# DC_Power_Regulation.net
KiCad netlist of a schematic drawn in Altium Designer
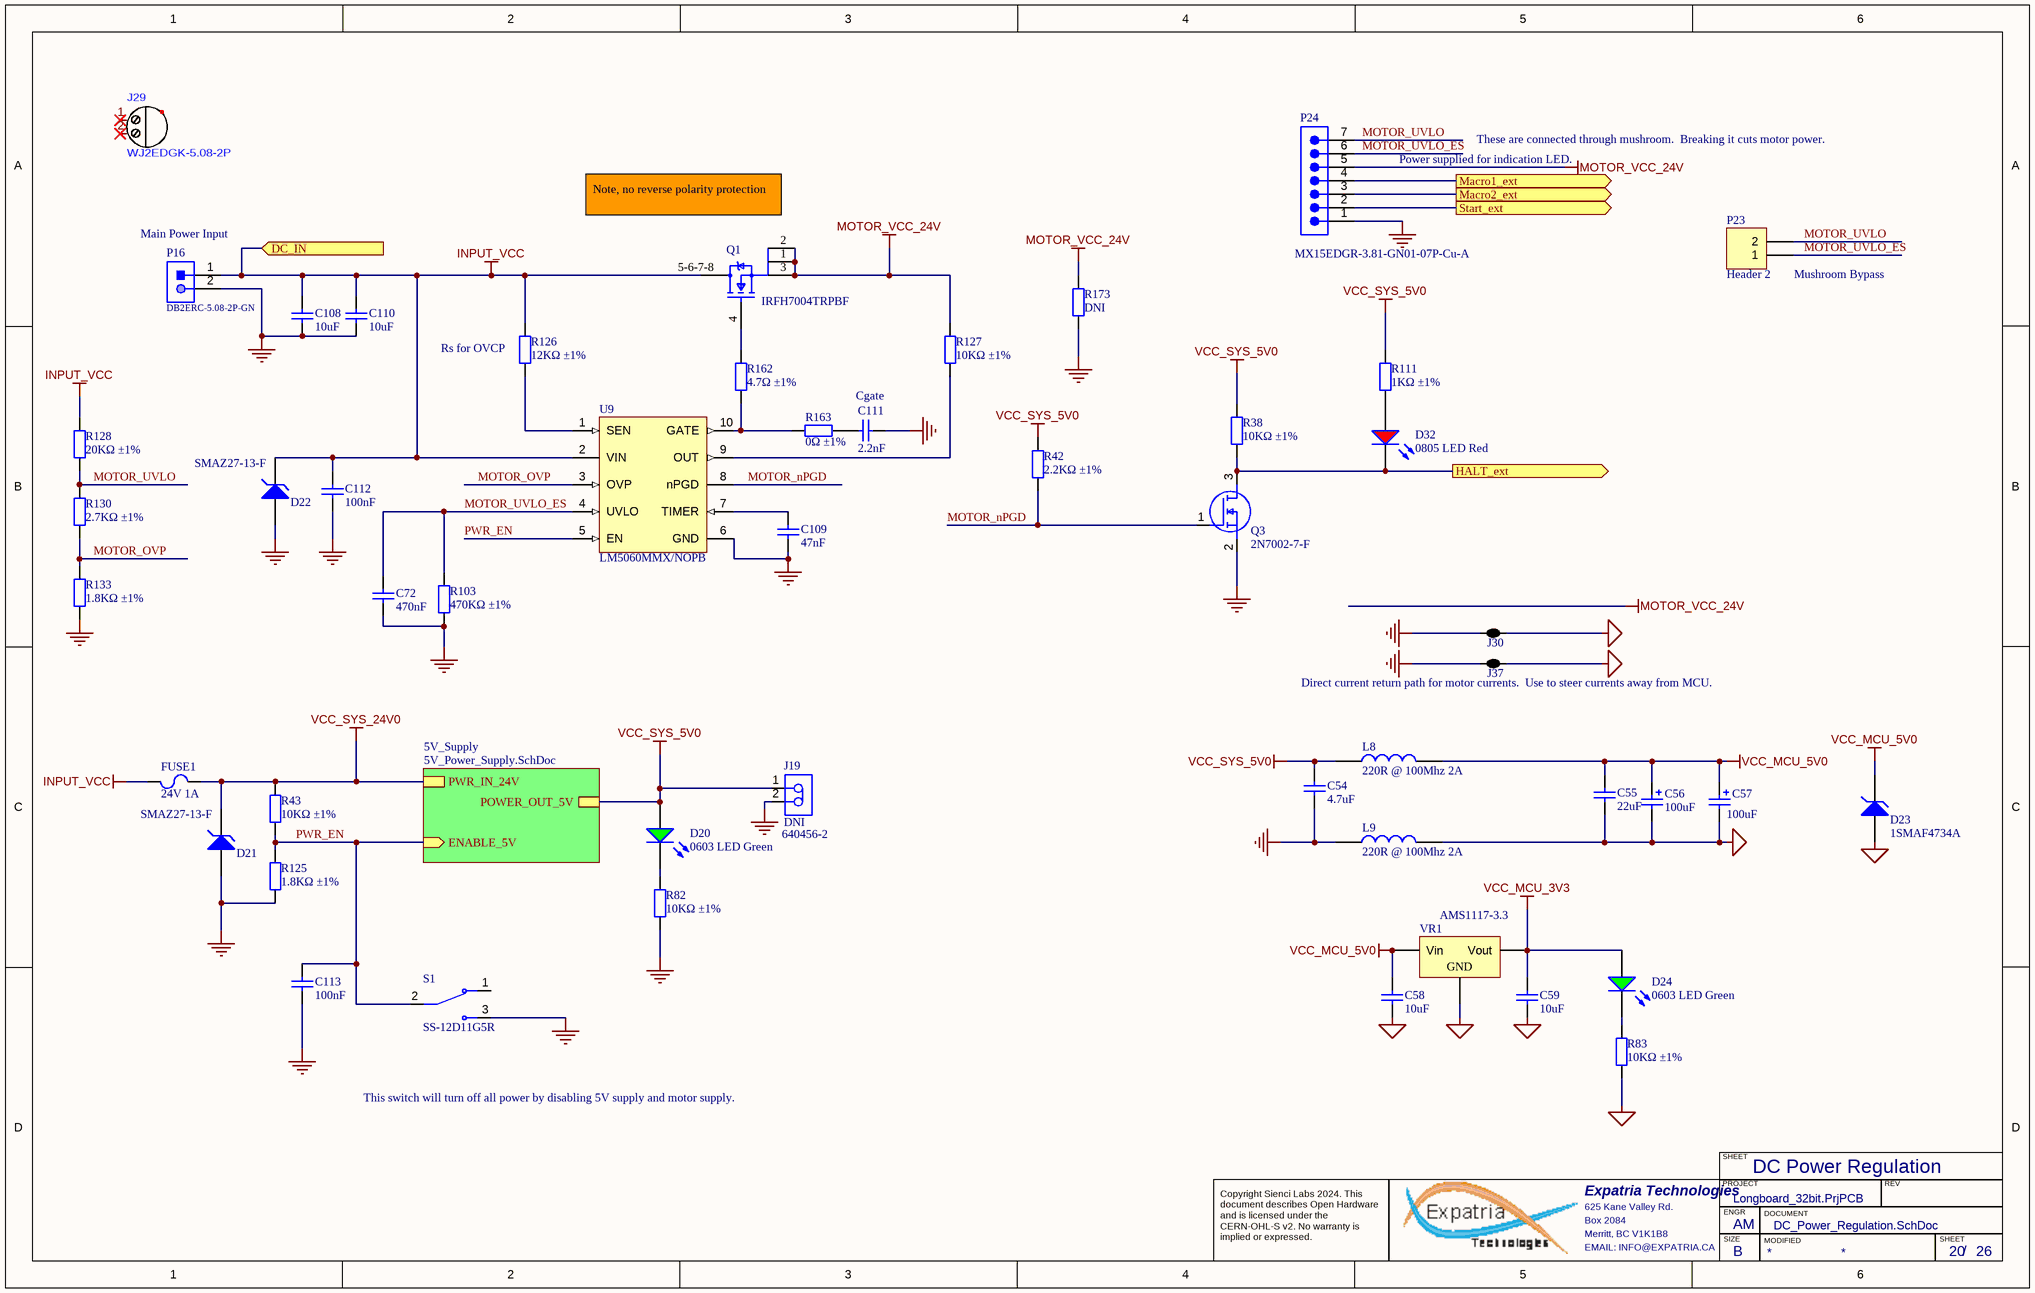
[diagram p0: DC_Power_Regulation.SchDoc]

(export (version "E")
  (design (tool "Eeschema 10.0.6"))
  (components
    (comp (ref "C54")
      (value "4.7uF")
      (footprint "0603_C")
      (description "16V 4.7uF X5R ±10% 0603 Multilayer Ceramic Capacitors MLCC - SMD/SMT ROHS")
      (fields (field (name "MANUFACTURER") "Samsung Electro-Mechanics") (field (name "TOLERANCE") "10%"))
      (libsource (lib "Sienci_Labs") (part "0603 4.7uF (475) 10% 16V"))
    )
    (comp (ref "C55")
      (value "22uF")
      (footprint "0805_C")
      (description "25V 22uF X5R ±20% 0805 Multilayer Ceramic Capacitors MLCC - SMD/SMT ROHS")
      (fields (field (name "MANUFACTURER") "Samsung Electro-Mechanics") (field (name "TOLERANCE") "20%"))
      (libsource (lib "Sienci_Labs") (part "0805 22uF (226) 20% 25V"))
    )
    (comp (ref "C56")
      (value "100uF")
      (footprint "CASE-B_3528")
      (description "Tantalum capacitor")
      (fields (field (name "MANUFACTURER") "AVX") (field (name "PARTNUMBER") "TAJB107K006RNJ"))
      (libsource (lib "Cap") (part "3528 100uF (107) 10% 6.3V"))
    )
    (comp (ref "C57")
      (value "100uF")
      (footprint "WCAP-ASLI_D6.3H7.7")
      (fields
        (field (name "MANUFACTURER") "Capxon International Elec")
        (field (name "MANUFACTURER PART NUMBER") "HV101M035E077ETR")
      )
      (libsource (lib "IQAnalog") (part "865080445010"))
    )
    (comp (ref "C58")
      (value "10uF")
      (footprint "1206_C")
      (description "50V 10uF X5R ±10% 1206 Multilayer Ceramic Capacitors MLCC - SMD/SMT ROHS")
      (fields
        (field (name "MANUFACTURER") "Samsung Electro-Mechanics")
        (field (name "MANUFACTURER PART NUMBER") "CL31A106KBHNNNE")
      )
      (libsource (lib "Sienci_Labs") (part "1206 10uF (106) 10% 50V"))
    )
    (comp (ref "C59")
      (value "10uF")
      (footprint "1206_C")
      (description "50V 10uF X5R ±10% 1206 Multilayer Ceramic Capacitors MLCC - SMD/SMT ROHS")
      (fields
        (field (name "MANUFACTURER") "Samsung Electro-Mechanics")
        (field (name "MANUFACTURER PART NUMBER") "CL31A106KBHNNNE")
      )
      (libsource (lib "Sienci_Labs") (part "1206 10uF (106) 10% 50V"))
    )
    (comp (ref "C72")
      (value "470nF")
      (footprint "0603_C")
      (description "Chip capacitors")
      (fields (field (name "MANUFACTURER") "Samsung Electro-Mechanics") (field (name "TOLERANCE") "10%"))
      (libsource (lib "Sienci_Labs") (part "0603 470nF (474) 10% 25V"))
    )
    (comp (ref "C108")
      (value "10uF")
      (footprint "1206_C")
      (description "50V 10uF X5R ±10% 1206 Multilayer Ceramic Capacitors MLCC - SMD/SMT ROHS")
      (fields (field (name "MANUFACTURER") "Samsung Electro-Mechanics") (field (name "TOLERANCE") "10%"))
      (libsource (lib "Sienci_Labs") (part "1206 10uF (106) 10% 50V"))
    )
    (comp (ref "C109")
      (value "47nF")
      (footprint "0603_C")
      (description "Chip capacitors")
      (fields
        (field (name "MANUFACTURER") "Samsung Electro-Mechanics")
        (field (name "PARTNUMBER") "CL10B473KB8NNNC")
      )
      (libsource (lib "Cap") (part "0603 47nF (473) 10% 50V"))
    )
    (comp (ref "C110")
      (value "10uF")
      (footprint "1206_C")
      (description "50V 10uF X5R ±10% 1206 Multilayer Ceramic Capacitors MLCC - SMD/SMT ROHS")
      (fields (field (name "MANUFACTURER") "Samsung Electro-Mechanics") (field (name "TOLERANCE") "10%"))
      (libsource (lib "Sienci_Labs") (part "1206 10uF (106) 10% 50V"))
    )
    (comp (ref "C111")
      (value "2.2nF")
      (footprint "0402_C")
      (description "Chip capacitor")
      (fields
        (field (name "MANUFACTURER") "Guangdong Fenghua Advanced Tech")
        (field (name "TOLERANCE") "10%")
      )
      (libsource (lib "Cap") (part "0402 2.2nF (222) 10% 50V"))
    )
    (comp (ref "C112")
      (value "100nF")
      (footprint "0603_C")
      (description "50V 100nF X7R ±10% 0603 Multilayer Ceramic Capacitors MLCC - SMD/SMT ROHS")
      (fields (field (name "MANUFACTURER") "YAGEO") (field (name "TOLERANCE") "10%"))
      (libsource (lib "Sienci_Labs") (part "0603 100nF (104) 10% 50V"))
    )
    (comp (ref "C113")
      (value "100nF")
      (footprint "0603_C")
      (description "50V 100nF X7R ±10% 0603 Multilayer Ceramic Capacitors MLCC - SMD/SMT ROHS")
      (fields (field (name "MANUFACTURER") "YAGEO") (field (name "TOLERANCE") "10%"))
      (libsource (lib "Sienci_Labs") (part "0603 100nF (104) 10% 50V"))
    )
    (comp (ref "D20")
      (value "0603 LED Green")
      (footprint "0603_LED_S1 - GREEN")
      (fields
        (field (name "MANUFACTURER PART NUMBER") "19-217/GHC-YR1S2/3T")
        (field (name "MANUFACTURER") "Everlight Elec")
      )
      (libsource (lib "Sienci_Labs") (part "19-217/GHC-YR1S2/3T"))
    )
    (comp (ref "D21")
      (value "SMAZ27-13-F")
      (footprint "DIOM5226X240N")
      (description "27V ±5% 1W 500nA @ 20.5V SMA(DO-214AC) Zener Diodes RoHS")
      (fields (field (name "MANUFACTURER") "Diodes Incorporated"))
      (libsource (lib "PrintNC_GRBLHAL_Breakout") (part "BZT52C27"))
    )
    (comp (ref "D22")
      (value "SMAZ27-13-F")
      (footprint "DIOM5226X240N")
      (description "27V ±5% 1W 500nA @ 20.5V SMA(DO-214AC) Zener Diodes RoHS")
      (fields (field (name "MANUFACTURER") "Diodes Incorporated"))
      (libsource (lib "PrintNC_GRBLHAL_Breakout") (part "BZT52C27"))
    )
    (comp (ref "D23")
      (value "1SMAF4734A")
      (footprint "DIOM5226X240N")
      (description "27V ±5% 1W 500nA @ 20.5V SMA(DO-214AC) Zener Diodes RoHS")
      (fields (field (name "MANUFACTURER") "Shandong Jingdao Microelectronics"))
      (libsource (lib "PrintNC_GRBLHAL_Breakout") (part "BZT52C27"))
    )
    (comp (ref "D24")
      (value "0603 LED Green")
      (footprint "0603_LED_S1 - GREEN")
      (fields
        (field (name "MANUFACTURER PART NUMBER") "19-217/GHC-YR1S2/3T")
        (field (name "MANUFACTURER") "Everlight Elec")
      )
      (libsource (lib "Sienci_Labs") (part "19-217/GHC-YR1S2/3T"))
    )
    (comp (ref "D32")
      (value "0805 LED Red")
      (footprint "0805_LED_S1 - RED")
      (description "Red 0805 Light Emitting Diodes (LED) ROHS")
      (fields
        (field (name "MANUFACTURER") "Foshan NationStar Optoelectronics")
        (field (name "MANUFACTURER PART NUMBER") "NCD0805R1")
      )
      (libsource (lib "Sienci_Labs") (part "0805 LED Red"))
    )
    (comp (ref "FUSE1")
      (value "24V 1A")
      (footprint "1206_C")
      (description "24V 1A 0.1s 1206 PTC Resettable Fuses RoHS")
      (fields
        (field (name "MANUFACTURER") "Jinrui Electronic Materials Co.")
        (field (name "PARTNUMBER") "JK-nSMD050-24")
      )
      (libsource (lib "PrintNC_GRBLHAL_Breakout") (part "JK-nSMD050-24"))
    )
    (comp (ref "J19")
      (value "DNI")
      (footprint "TECO-640456-2_V")
      (fields (field (name "MANUFACTURER") "TE Connectivity") (field (name "ALTIUM_VALUE") "640456-2"))
      (libsource (lib "Altium Content Vault") (part "CN-2P-F-QF2"))
    )
    (comp (ref "J29")
      (value "WJ2EDGK-5.08-2P")
      (description "5.08mm Green Plug P=5.08mm Pluggable System Terminal Block ROHS")
      (fields (field (name "MANUFACTURER") "Kangnex"))
      (libsource (lib "Sienci_Labs") (part "WJ2EDGK-5.08-2P"))
    )
    (comp (ref "J30")
      (value "2 way net tie junction")
      (footprint "2way_HP")
      (libsource (lib "NetTie") (part "2way"))
    )
    (comp (ref "J37")
      (value "2 way net tie junction")
      (footprint "2way_HP")
      (libsource (lib "NetTie") (part "2way"))
    )
    (comp (ref "L8")
      (value "220R @ 100Mhz 2A")
      (footprint "0805_R")
      (description "150mΩ ±25% 220Ω@100MHz 0805 Ferrite Beads ROHS")
      (fields
        (field (name "MANUFACTURER PART NUMBER") "CBW201209U221T")
        (field (name "MANUFACTURER") "FH (Guangdong Fenghua Advanced Tech)")
      )
      (libsource (lib "Sienci_Labs") (part "CBW201209U221T"))
    )
    (comp (ref "L9")
      (value "220R @ 100Mhz 2A")
      (footprint "0805_R")
      (description "150mΩ ±25% 220Ω@100MHz 0805 Ferrite Beads ROHS")
      (fields
        (field (name "MANUFACTURER PART NUMBER") "CBW201209U221T")
        (field (name "MANUFACTURER") "FH (Guangdong Fenghua Advanced Tech)")
      )
      (libsource (lib "Sienci_Labs") (part "CBW201209U221T"))
    )
    (comp (ref "P16")
      (value "DB2ERC-5.08-2P-GN")
      (footprint "CONN-TH_2P-P5.08_DB2ERC-5.08-2P")
      (fields (field (name "MANUFACTURER") "Dibo"))
      (libsource (lib "Sienci_Labs") (part "DB2ERC-5.08-2P-GN"))
    )
    (comp (ref "P23")
      (value "Header 2")
      (footprint "HDR1X2")
      (description "Straight Square Pins 2 2.54mm Black Brass 1x2P Plugin,P=2.54mm Pin Headers ROHS")
      (fields
        (field (name "MANUFACTURER") "MOLEX")
        (field (name "MANUFACTURER PART NUMBER") "22284020")
        (field (name "PUBLISHER") "Altium Limited")
      )
      (libsource (lib "Sienci_Labs") (part "Header 2"))
    )
    (comp (ref "P24")
      (value "MX15EDGR-3.81-GN01-07P-Cu-A")
      (footprint "691322310007")
      (fields (field (name "MANUFACTURER") "MAX"))
      (libsource (lib "Sienci_Labs") (part "MX15EDGR-3.81-GN01-07P-Cu-A"))
    )
    (comp (ref "Q1")
      (value "IRFH7004TRPBF")
      (footprint "FP-PG-TDSON-8-MFG")
      (description "MOSFET N-CH 40V 100A 8PQFN")
      (libsource (lib "MOS") (part "IRFH7004TRPBF"))
    )
    (comp (ref "Q3")
      (value "2N7002-7-F")
      (footprint "SOT-23(SOT-23-3)")
      (description "60V 115mA 7.5Ω@5V,50mA 370mW N Channel SOT-23 MOSFETs ROHS")
      (fields (field (name "MANUFACTURER") "Diodes Inc.") (field (name "MOUSER PART NUMBER") "621-2N7002-F"))
      (libsource (lib "Sienci_Labs") (part "2N7002-7-F"))
    )
    (comp (ref "R38")
      (value "10KΩ ±1%")
      (footprint "0603_R")
      (description "Chip resistor")
      (fields (field (name "MANUFACTURER") "Uniroyal Elec") (field (name "PARTNUMBER") "0603WAF1002T5E"))
      (libsource (lib "RES") (part "0603 10K (1002) 1%"))
    )
    (comp (ref "R42")
      (value "2.2KΩ ±1%")
      (footprint "0603_R")
      (description "Chip resistor")
      (fields (field (name "MANUFACTURER") "Uniroyal Elec") (field (name "PARTNUMBER") "0603WAF2201T5E"))
      (libsource (lib "RES") (part "0603 2.2K (2201) 1%"))
    )
    (comp (ref "R43")
      (value "10KΩ ±1%")
      (footprint "0603_R")
      (description "Chip resistor")
      (fields (field (name "MANUFACTURER") "Uniroyal Elec") (field (name "PARTNUMBER") "0603WAF1002T5E"))
      (libsource (lib "RES") (part "0603 10K (1002) 1%"))
    )
    (comp (ref "R82")
      (value "10KΩ ±1%")
      (footprint "0603_R")
      (description "Chip resistor")
      (fields (field (name "MANUFACTURER") "Uniroyal Elec") (field (name "PARTNUMBER") "0603WAF1002T5E"))
      (libsource (lib "RES") (part "0603 10K (1002) 1%"))
    )
    (comp (ref "R83")
      (value "10KΩ ±1%")
      (footprint "0603_R")
      (description "Chip resistor")
      (fields (field (name "MANUFACTURER") "Uniroyal Elec") (field (name "PARTNUMBER") "0603WAF1002T5E"))
      (libsource (lib "RES") (part "0603 10K (1002) 1%"))
    )
    (comp (ref "R103")
      (value "470KΩ ±1%")
      (footprint "0603_R")
      (description "Chip resistor")
      (fields (field (name "MANUFACTURER") "Uniroyal Elec") (field (name "PARTNUMBER") "0603WAF4703T5E"))
      (libsource (lib "RES") (part "0603 470K (4703) 1%"))
    )
    (comp (ref "R111")
      (value "1KΩ ±1%")
      (footprint "0603_R")
      (description "Chip resistor")
      (fields (field (name "MANUFACTURER") "Uniroyal Elec") (field (name "PARTNUMBER") "0603WAF1001T5E"))
      (libsource (lib "RES") (part "0603 1K (1001) 1%"))
    )
    (comp (ref "R125")
      (value "1.8KΩ ±1%")
      (footprint "0603_R")
      (description "Chip resistor")
      (fields (field (name "MANUFACTURER") "Uniroyal Elec") (field (name "PARTNUMBER") "0603WAF1801T5E"))
      (libsource (lib "RES") (part "0603 1.8K (1801) 1%"))
    )
    (comp (ref "R126")
      (value "12KΩ ±1%")
      (footprint "0603_R")
      (description "Chip resistor")
      (fields (field (name "MANUFACTURER") "Uniroyal Elec") (field (name "PARTNUMBER") "0603WAF1202T5E"))
      (libsource (lib "RES") (part "0603 12K (1202) 1%"))
    )
    (comp (ref "R127")
      (value "10KΩ ±1%")
      (footprint "0603_R")
      (description "Chip resistor")
      (fields (field (name "MANUFACTURER") "Uniroyal Elec") (field (name "PARTNUMBER") "0603WAF1002T5E"))
      (libsource (lib "RES") (part "0603 10K (1002) 1%"))
    )
    (comp (ref "R128")
      (value "20KΩ ±1%")
      (footprint "0603_R")
      (description "Chip resistor")
      (fields (field (name "MANUFACTURER") "Uniroyal Elec") (field (name "PARTNUMBER") "0603WAF2002T5E"))
      (libsource (lib "RES") (part "0603 20K (2002) 1%"))
    )
    (comp (ref "R130")
      (value "2.7KΩ ±1%")
      (footprint "0603_R")
      (description "Chip resistor")
      (fields (field (name "MANUFACTURER") "Uniroyal Elec") (field (name "PARTNUMBER") "0603WAF2701T5E"))
      (libsource (lib "RES") (part "0603 2.7K (2701) 1%"))
    )
    (comp (ref "R133")
      (value "1.8KΩ ±1%")
      (footprint "0603_R")
      (description "Chip resistor")
      (fields (field (name "MANUFACTURER") "Uniroyal Elec") (field (name "PARTNUMBER") "0603WAF1801T5E"))
      (libsource (lib "RES") (part "0603 1.8K (1801) 1%"))
    )
    (comp (ref "R162")
      (value "4.7Ω ±1%")
      (footprint "0603_R")
      (description "Chip resistor")
      (fields (field (name "MANUFACTURER") "Uniroyal Elec") (field (name "PARTNUMBER") "0603WAF470KT5E"))
      (libsource (lib "RES") (part "0603 4.7R (4R70) 1%"))
    )
    (comp (ref "R163")
      (value "0Ω ±1%")
      (footprint "0603_R")
      (description "Chip resistor")
      (fields (field (name "MANUFACTURER") "Uniroyal Elec") (field (name "PARTNUMBER") "0603WAF0000T5E"))
      (libsource (lib "RES") (part "0603 0R (0R0) 1%"))
    )
    (comp (ref "R173")
      (value "DNI")
      (footprint "0603_R")
      (description "Chip resistor")
      (fields (field (name "MANUFACTURER") "Uniroyal Elec") (field (name "PARTNUMBER") "0603WAF1002T5E"))
      (libsource (lib "RES") (part "0603 10K (1002) 1%"))
    )
    (comp (ref "S1")
      (value "SS-12D11G5R")
      (footprint "SW_500SSP1S1M6QEA")
      (description "Shrouded 5A SPDT 125V 125V 5A 10000次 Black Plugin Slide Switches ROHS")
      (fields (field (name "MANUFACTURER") "XKB Connectivity"))
      (libsource (lib "Sienci_Labs") (part "SS-12D11G5R"))
    )
    (comp (ref "U9")
      (value "LM5060MMX/NOPB")
      (footprint "DGS0010A_N")
      (fields (field (name "MANUFACTURER") "TI National Semiconductor"))
      (libsource (lib "Sienci_Labs") (part "LM5060MMX/NOPB"))
    )
    (comp (ref "VR1")
      (value "AMS1117-3.3")
      (footprint "SOT-223")
      (description "Vout=3.3V 1A 72dB@(120Hz) (LDO)")
      (fields (field (name "MANUFACTURER") "AMS"))
      (libsource (lib "LDO") (part "SOT-223 AMS1117-3.3"))
    )
  )
  (nets
    (net (code "1") (name "/HALT_ext") (class "Default")
      (node (ref "D32") (pin "K") (pinfunction "K_K") (pintype "passive"))
      (node (ref "Q3") (pin "3") (pinfunction "D_3") (pintype "passive"))
      (node (ref "R38") (pin "1") (pinfunction "1_1") (pintype "passive"))
    )
    (net (code "2") (name "/MOTOR_OVP") (class "Default")
      (node (ref "R130") (pin "1") (pinfunction "1_1") (pintype "passive"))
      (node (ref "R133") (pin "2") (pinfunction "2_2") (pintype "passive"))
      (node (ref "U9") (pin "3") (pinfunction "OVP_3") (pintype "input"))
    )
    (net (code "3") (name "/MOTOR_UVLO") (class "Default")
      (node (ref "P23") (pin "2") (pinfunction "2_2") (pintype "passive"))
      (node (ref "P24") (pin "7") (pinfunction "7_7") (pintype "passive"))
      (node (ref "R128") (pin "1") (pinfunction "1_1") (pintype "passive"))
      (node (ref "R130") (pin "2") (pinfunction "2_2") (pintype "passive"))
    )
    (net (code "4") (name "/MOTOR_UVLO_ES") (class "Default")
      (node (ref "C72") (pin "2") (pinfunction "2_2") (pintype "passive"))
      (node (ref "P23") (pin "1") (pinfunction "1_1") (pintype "passive"))
      (node (ref "P24") (pin "6") (pinfunction "6_6") (pintype "passive"))
      (node (ref "R103") (pin "2") (pinfunction "2_2") (pintype "passive"))
      (node (ref "U9") (pin "4") (pinfunction "UVLO_4") (pintype "input"))
    )
    (net (code "5") (name "/MOTOR_nPGD") (class "Default")
      (node (ref "Q3") (pin "1") (pinfunction "G_1") (pintype "passive"))
      (node (ref "R42") (pin "1") (pinfunction "1_1") (pintype "passive"))
      (node (ref "U9") (pin "8") (pinfunction "nPGD_8") (pintype "open_collector"))
    )
    (net (code "6") (name "/Macro1_ext") (class "Default")
      (node (ref "P24") (pin "4") (pinfunction "4_4") (pintype "passive"))
    )
    (net (code "7") (name "/Macro2_ext") (class "Default")
      (node (ref "P24") (pin "3") (pinfunction "3_3") (pintype "passive"))
    )
    (net (code "8") (name "/PWR_EN") (class "Default")
      (node (ref "C113") (pin "2") (pinfunction "2_2") (pintype "passive"))
      (node (ref "R125") (pin "2") (pinfunction "2_2") (pintype "passive"))
      (node (ref "R43") (pin "1") (pinfunction "1_1") (pintype "passive"))
      (node (ref "S1") (pin "2") (pinfunction "COM_2") (pintype "passive"))
      (node (ref "U9") (pin "5") (pinfunction "EN_5") (pintype "input"))
    )
    (net (code "9") (name "/Start_ext") (class "Default")
      (node (ref "P24") (pin "2") (pinfunction "2_2") (pintype "passive"))
    )
    (net (code "10") (name "GND") (class "Default")
      (node (ref "C108") (pin "1") (pinfunction "1_1") (pintype "passive"))
      (node (ref "C109") (pin "1") (pinfunction "1_1") (pintype "passive"))
      (node (ref "C110") (pin "1") (pinfunction "1_1") (pintype "passive"))
      (node (ref "C111") (pin "1") (pinfunction "1_1") (pintype "passive"))
      (node (ref "C112") (pin "1") (pinfunction "1_1") (pintype "passive"))
      (node (ref "C113") (pin "1") (pinfunction "1_1") (pintype "passive"))
      (node (ref "C54") (pin "1") (pinfunction "1_1") (pintype "passive"))
      (node (ref "C72") (pin "1") (pinfunction "1_1") (pintype "passive"))
      (node (ref "D21") (pin "1") (pinfunction "A_1") (pintype "passive"))
      (node (ref "D22") (pin "1") (pinfunction "A_1") (pintype "passive"))
      (node (ref "J19") (pin "2") (pinfunction "2_2") (pintype "passive"))
      (node (ref "J30") (pin "1") (pinfunction "1_1") (pintype "passive"))
      (node (ref "J37") (pin "1") (pinfunction "1_1") (pintype "passive"))
      (node (ref "L9") (pin "1") (pinfunction "1_1") (pintype "passive"))
      (node (ref "P16") (pin "2") (pinfunction "2_2") (pintype "passive"))
      (node (ref "P24") (pin "1") (pinfunction "1_1") (pintype "passive"))
      (node (ref "Q3") (pin "2") (pinfunction "S_2") (pintype "passive"))
      (node (ref "R103") (pin "1") (pinfunction "1_1") (pintype "passive"))
      (node (ref "R125") (pin "1") (pinfunction "1_1") (pintype "passive"))
      (node (ref "R133") (pin "1") (pinfunction "1_1") (pintype "passive"))
      (node (ref "R173") (pin "1") (pinfunction "1_1") (pintype "passive"))
      (node (ref "R82") (pin "1") (pinfunction "1_1") (pintype "passive"))
      (node (ref "S1") (pin "3") (pinfunction "NO_3") (pintype "passive"))
      (node (ref "U9") (pin "6") (pinfunction "GND_6") (pintype "power_in"))
    )
    (net (code "11") (name "INPUT_VCC") (class "Default")
      (node (ref "C108") (pin "2") (pinfunction "2_2") (pintype "passive"))
      (node (ref "C110") (pin "2") (pinfunction "2_2") (pintype "passive"))
      (node (ref "C112") (pin "2") (pinfunction "2_2") (pintype "passive"))
      (node (ref "D22") (pin "2") (pinfunction "K_2") (pintype "passive"))
      (node (ref "FUSE1") (pin "1") (pinfunction "1_1") (pintype "passive"))
      (node (ref "P16") (pin "1") (pinfunction "1_1") (pintype "passive"))
      (node (ref "Q1") (pin "5-6-7-8") (pinfunction "D_5-6-7-8") (pintype "passive"))
      (node (ref "R126") (pin "2") (pinfunction "2_2") (pintype "passive"))
      (node (ref "R128") (pin "2") (pinfunction "2_2") (pintype "passive"))
      (node (ref "U9") (pin "2") (pinfunction "VIN_2") (pintype "power_in"))
    )
    (net (code "12") (name "MCU_GND") (class "Default")
      (node (ref "C55") (pin "1") (pinfunction "1_1") (pintype "passive"))
      (node (ref "C56") (pin "2") (pinfunction "2_2") (pintype "passive"))
      (node (ref "C57") (pin "2") (pinfunction "N_2") (pintype "passive"))
      (node (ref "C58") (pin "1") (pinfunction "1_1") (pintype "passive"))
      (node (ref "C59") (pin "1") (pinfunction "1_1") (pintype "passive"))
      (node (ref "D23") (pin "1") (pinfunction "A_1") (pintype "passive"))
      (node (ref "J30") (pin "2") (pinfunction "2_2") (pintype "passive"))
      (node (ref "J37") (pin "2") (pinfunction "2_2") (pintype "passive"))
      (node (ref "L9") (pin "2") (pinfunction "2_2") (pintype "passive"))
      (node (ref "R83") (pin "1") (pinfunction "1_1") (pintype "passive"))
      (node (ref "VR1") (pin "1") (pinfunction "GND_1") (pintype "passive"))
    )
    (net (code "13") (name "MOTOR_VCC_24V") (class "Default")
      (node (ref "P24") (pin "5") (pinfunction "5_5") (pintype "passive"))
      (node (ref "Q1") (pin "1") (pinfunction "S_1") (pintype "passive"))
      (node (ref "Q1") (pin "2") (pinfunction "S_2") (pintype "passive"))
      (node (ref "Q1") (pin "3") (pinfunction "S_3") (pintype "passive"))
      (node (ref "R127") (pin "2") (pinfunction "2_2") (pintype "passive"))
      (node (ref "R173") (pin "2") (pinfunction "2_2") (pintype "passive"))
    )
    (net (code "14") (name "Net-(C111-Pad2)") (class "Default")
      (node (ref "C111") (pin "2") (pinfunction "2_2") (pintype "passive"))
      (node (ref "R163") (pin "1") (pinfunction "1_1") (pintype "passive"))
    )
    (net (code "15") (name "Net-(D20-PadK)") (class "Default")
      (node (ref "D20") (pin "K") (pinfunction "K_K") (pintype "passive"))
      (node (ref "R82") (pin "2") (pinfunction "2_2") (pintype "passive"))
    )
    (net (code "16") (name "Net-(D24-PadK)") (class "Default")
      (node (ref "D24") (pin "K") (pinfunction "K_K") (pintype "passive"))
      (node (ref "R83") (pin "2") (pinfunction "2_2") (pintype "passive"))
    )
    (net (code "17") (name "Net-(D32-PadA)") (class "Default")
      (node (ref "D32") (pin "A") (pinfunction "A_A") (pintype "passive"))
      (node (ref "R111") (pin "1") (pinfunction "1_1") (pintype "passive"))
    )
    (net (code "18") (name "Net-(Q1-G)") (class "Default")
      (node (ref "Q1") (pin "4") (pinfunction "G_4") (pintype "passive"))
      (node (ref "R162") (pin "2") (pinfunction "2_2") (pintype "passive"))
    )
    (net (code "19") (name "Net-(U9-GATE)") (class "Default")
      (node (ref "R162") (pin "1") (pinfunction "1_1") (pintype "passive"))
      (node (ref "R163") (pin "2") (pinfunction "2_2") (pintype "passive"))
      (node (ref "U9") (pin "10") (pinfunction "GATE_10") (pintype "output"))
    )
    (net (code "20") (name "Net-(U9-OUT)") (class "Default")
      (node (ref "R127") (pin "1") (pinfunction "1_1") (pintype "passive"))
      (node (ref "U9") (pin "9") (pinfunction "OUT_9") (pintype "output"))
    )
    (net (code "21") (name "Net-(U9-SEN)") (class "Default")
      (node (ref "R126") (pin "1") (pinfunction "1_1") (pintype "passive"))
      (node (ref "U9") (pin "1") (pinfunction "SEN_1") (pintype "input"))
    )
    (net (code "22") (name "Net-(U9-TIMER)") (class "Default")
      (node (ref "C109") (pin "2") (pinfunction "2_2") (pintype "passive"))
      (node (ref "U9") (pin "7") (pinfunction "TIMER_7") (pintype "input"))
    )
    (net (code "23") (name "VCC_MCU_3V3") (class "Default")
      (node (ref "C59") (pin "2") (pinfunction "2_2") (pintype "passive"))
      (node (ref "D24") (pin "A") (pinfunction "A_A") (pintype "passive"))
      (node (ref "VR1") (pin "2") (pinfunction "Vout_2") (pintype "passive"))
    )
    (net (code "24") (name "VCC_MCU_5V0") (class "Default")
      (node (ref "C55") (pin "2") (pinfunction "2_2") (pintype "passive"))
      (node (ref "C56") (pin "1") (pinfunction "1_1") (pintype "passive"))
      (node (ref "C57") (pin "1") (pinfunction "P_1") (pintype "passive"))
      (node (ref "C58") (pin "2") (pinfunction "2_2") (pintype "passive"))
      (node (ref "D23") (pin "2") (pinfunction "K_2") (pintype "passive"))
      (node (ref "L8") (pin "2") (pinfunction "2_2") (pintype "passive"))
      (node (ref "VR1") (pin "3") (pinfunction "Vin_3") (pintype "passive"))
    )
    (net (code "25") (name "VCC_SYS_5V0") (class "Default")
      (node (ref "C54") (pin "2") (pinfunction "2_2") (pintype "passive"))
      (node (ref "D20") (pin "A") (pinfunction "A_A") (pintype "passive"))
      (node (ref "J19") (pin "1") (pinfunction "1_1") (pintype "passive"))
      (node (ref "L8") (pin "1") (pinfunction "1_1") (pintype "passive"))
      (node (ref "R111") (pin "2") (pinfunction "2_2") (pintype "passive"))
      (node (ref "R38") (pin "2") (pinfunction "2_2") (pintype "passive"))
      (node (ref "R42") (pin "2") (pinfunction "2_2") (pintype "passive"))
    )
    (net (code "26") (name "VCC_SYS_24V0") (class "Default")
      (node (ref "D21") (pin "2") (pinfunction "K_2") (pintype "passive"))
      (node (ref "FUSE1") (pin "2") (pinfunction "2_2") (pintype "passive"))
      (node (ref "R43") (pin "2") (pinfunction "2_2") (pintype "passive"))
    )
    (net (code "27") (name "unconnected-(J29-Pad1)") (class "Default")
      (node (ref "J29") (pin "1") (pinfunction "1_1") (pintype "passive+no_connect"))
    )
    (net (code "28") (name "unconnected-(J29-Pad2)") (class "Default")
      (node (ref "J29") (pin "2") (pinfunction "2_2") (pintype "passive+no_connect"))
    )
    (net (code "29") (name "unconnected-(S1-NC-Pad1)") (class "Default")
      (node (ref "S1") (pin "1") (pinfunction "NC_1") (pintype "passive"))
    )
  )
)
